# design.net
KiCad netlist of a schematic drawn in EasyEDA
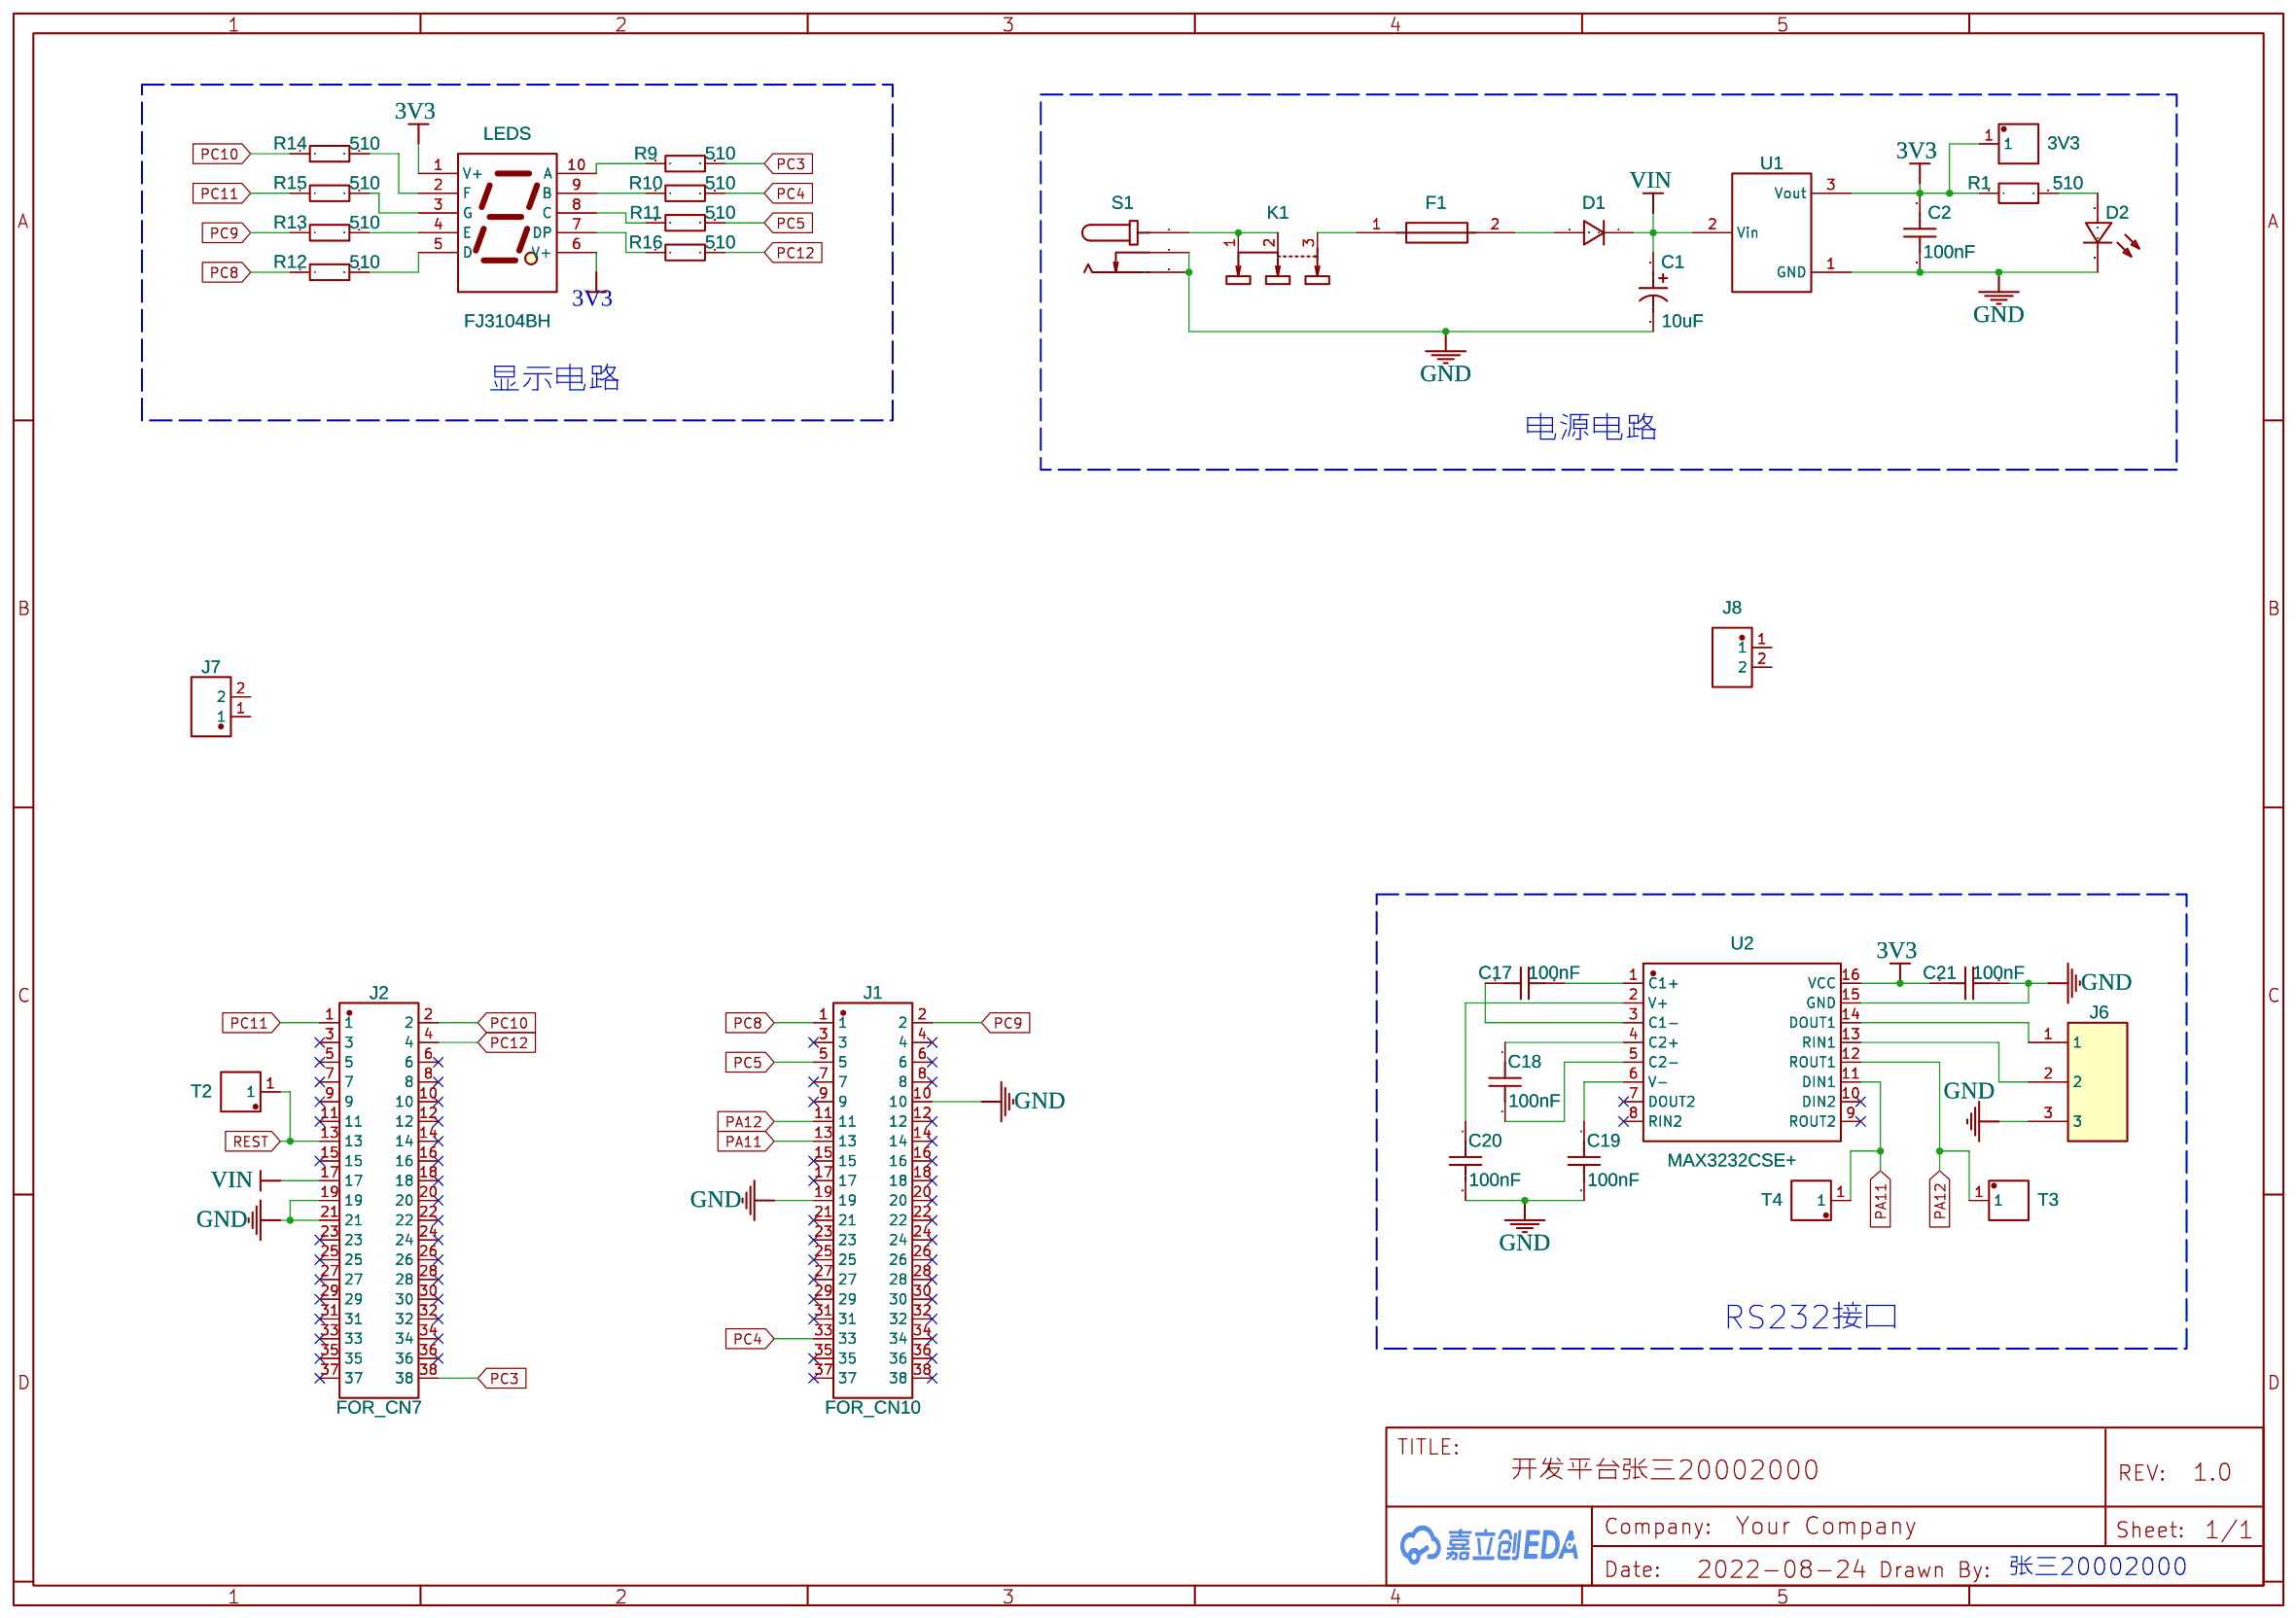
[diagram p0: schematic sheet]

(export (version "E")
  (design (tool "Eeschema 10.0.6"))
  (components
    (comp (ref "3V3")
      (value "54101-T06-00")
      (fields (field (name "BOM_Supplier Part") "C213463"))
      (libsource (lib "") (part "54101-T06-00"))
    )
    (comp (ref "C1")
      (value "10uF")
      (fields
        (field (name "BOM_Manufacturer Part") "50V10uF CD110")
        (field (name "BOM_Supplier Part") "C2960200")
      )
      (libsource (lib "") (part "50V10UF CD110"))
    )
    (comp (ref "C2")
      (value "100nF")
      (fields
        (field (name "BOM_Manufacturer Part") "CT4-0805B104K500F3")
        (field (name "BOM_Supplier Part") "C84772")
      )
      (libsource (lib "") (part "CT4-0805B104K500F3_1"))
    )
    (comp (ref "C17")
      (value "100nF")
      (fields
        (field (name "BOM_Manufacturer Part") "CT4-0805B104K500F3")
        (field (name "BOM_Supplier Part") "C84772")
      )
      (libsource (lib "") (part "CT4-0805B104K500F3"))
    )
    (comp (ref "C18")
      (value "100nF")
      (fields
        (field (name "BOM_Manufacturer Part") "CT4-0805B104K500F3")
        (field (name "BOM_Supplier Part") "C84772")
      )
      (libsource (lib "") (part "CT4-0805B104K500F3_1"))
    )
    (comp (ref "C19")
      (value "100nF")
      (fields
        (field (name "BOM_Manufacturer Part") "CT4-0805B104K500F3")
        (field (name "BOM_Supplier Part") "C84772")
      )
      (libsource (lib "") (part "CT4-0805B104K500F3_1"))
    )
    (comp (ref "C20")
      (value "100nF")
      (fields
        (field (name "BOM_Manufacturer Part") "CT4-0805B104K500F3")
        (field (name "BOM_Supplier Part") "C84772")
      )
      (libsource (lib "") (part "CT4-0805B104K500F3_1"))
    )
    (comp (ref "C21")
      (value "100nF")
      (fields
        (field (name "BOM_Manufacturer Part") "CT4-0805B104K500F3")
        (field (name "BOM_Supplier Part") "C84772")
      )
      (libsource (lib "") (part "CT4-0805B104K500F3"))
    )
    (comp (ref "D1")
      (value "1N5817_C169165")
      (fields (field (name "BOM_Manufacturer Part") "1N5817") (field (name "BOM_Supplier Part") "C169165"))
      (libsource (lib "") (part "1N5817_C169165"))
    )
    (comp (ref "D2")
      (value "TJ-L3FYTGHTFCLFLC2R-A5")
      (fields (field (name "BOM_Supplier Part") "C330746"))
      (libsource (lib "") (part "TJ-L3FYTGHTFCLFLC2R-A5"))
    )
    (comp (ref "F1")
      (value "A72-065")
      (fields (field (name "BOM_Supplier Part") "C135426"))
      (libsource (lib "") (part "A72-065"))
    )
    (comp (ref "J1")
      (value "FOR_CN10")
      (fields
        (field (name "BOM_Manufacturer Part") "PM254-2-19-Z-8.5")
        (field (name "BOM_Supplier Part") "C2897420")
      )
      (libsource (lib "") (part "PM254-2-19-Z-8.5"))
    )
    (comp (ref "J2")
      (value "FOR_CN7")
      (fields
        (field (name "BOM_Manufacturer Part") "PM254-2-19-Z-8.5")
        (field (name "BOM_Supplier Part") "C2897420")
      )
      (libsource (lib "") (part "PM254-2-19-Z-8.5"))
    )
    (comp (ref "J6")
      (value "WJ124-3.81-3P")
      (fields (field (name "BOM_Supplier Part") "C36780"))
      (libsource (lib "") (part "WJ124-3.81-3P"))
    )
    (comp (ref "J7")
      (value "WJ124-3.81-2P")
      (fields (field (name "BOM_Supplier Part") "C69811"))
      (libsource (lib "") (part "WJ124-3.81-2P_1"))
    )
    (comp (ref "J8")
      (value "WJ124-3.81-2P")
      (fields (field (name "BOM_Supplier Part") "C69811"))
      (libsource (lib "") (part "WJ124-3.81-2P"))
    )
    (comp (ref "K1")
      (value "SS-12D10L5")
      (fields (field (name "BOM_Supplier Part") "C319012"))
      (libsource (lib "") (part "SS-12D10L5"))
    )
    (comp (ref "LEDS")
      (value "FJ3104BH")
      (fields (field (name "BOM_Supplier Part") "C2938319"))
      (libsource (lib "") (part "FJ3104BH"))
    )
    (comp (ref "R1")
      (value "510")
      (fields
        (field (name "BOM_Manufacturer Part") "MF1/8W-10KΩ±1%T52")
        (field (name "BOM_Supplier Part") "C713919")
      )
      (libsource (lib "") (part "MF1/8W-10KΩ±1%T52"))
    )
    (comp (ref "R9")
      (value "510")
      (fields (field (name "BOM_Supplier Part") "C119149"))
      (libsource (lib "") (part "MF1/8W-43Ω±1% T52"))
    )
    (comp (ref "R10")
      (value "510")
      (fields (field (name "BOM_Supplier Part") "C119149"))
      (libsource (lib "") (part "MF1/8W-43Ω±1% T52"))
    )
    (comp (ref "R11")
      (value "510")
      (fields (field (name "BOM_Supplier Part") "C119149"))
      (libsource (lib "") (part "MF1/8W-43Ω±1% T52"))
    )
    (comp (ref "R12")
      (value "510")
      (fields (field (name "BOM_Supplier Part") "C119149"))
      (libsource (lib "") (part "MF1/8W-43Ω±1% T52"))
    )
    (comp (ref "R13")
      (value "510")
      (fields (field (name "BOM_Supplier Part") "C119149"))
      (libsource (lib "") (part "MF1/8W-43Ω±1% T52"))
    )
    (comp (ref "R14")
      (value "510")
      (fields (field (name "BOM_Supplier Part") "C119149"))
      (libsource (lib "") (part "MF1/8W-43Ω±1% T52"))
    )
    (comp (ref "R15")
      (value "510")
      (fields (field (name "BOM_Supplier Part") "C119149"))
      (libsource (lib "") (part "MF1/8W-43Ω±1% T52"))
    )
    (comp (ref "R16")
      (value "510")
      (fields (field (name "BOM_Supplier Part") "C119149"))
      (libsource (lib "") (part "MF1/8W-43Ω±1% T52"))
    )
    (comp (ref "S1")
      (value "JPD1030-N521-4F")
      (fields (field (name "BOM_Supplier Part") "C426213"))
      (libsource (lib "") (part "JPD1030-N521-4F"))
    )
    (comp (ref "T2")
      (value "54101-T06-00")
      (fields (field (name "BOM_Supplier Part") "C213463"))
      (libsource (lib "") (part "54101-T06-00_2"))
    )
    (comp (ref "T3")
      (value "54101-T06-00")
      (fields (field (name "BOM_Supplier Part") "C213463"))
      (libsource (lib "") (part "54101-T06-00_1"))
    )
    (comp (ref "T4")
      (value "54101-T06-00")
      (fields (field (name "BOM_Supplier Part") "C213463"))
      (libsource (lib "") (part "54101-T06-00_2"))
    )
    (comp (ref "U1")
      (value "HT7533-1_C32617")
      (fields (field (name "BOM_Manufacturer Part") "HT7533-1") (field (name "BOM_Supplier Part") "C32617"))
      (libsource (lib "") (part "HT7533-1_C32617"))
    )
    (comp (ref "U2")
      (value "MAX3232CSE+")
      (fields (field (name "BOM_Supplier Part") "C143430"))
      (libsource (lib "") (part "MAX3232CSE+"))
    )
  )
  (nets
    (net (code "1") (name "3V3") (class "Default")
      (node (ref "3V3") (pin "1") (pinfunction "1_1") (pintype "unspecified"))
      (node (ref "C2") (pin "1") (pinfunction "1_1") (pintype "unspecified"))
      (node (ref "C21") (pin "1") (pinfunction "1_1") (pintype "unspecified"))
      (node (ref "LEDS") (pin "1") (pinfunction "V+_1") (pintype "unspecified"))
      (node (ref "LEDS") (pin "6") (pinfunction "V+_6") (pintype "unspecified"))
      (node (ref "R1") (pin "1") (pinfunction "1_1") (pintype "unspecified"))
      (node (ref "U1") (pin "3") (pinfunction "Vout_3") (pintype "unspecified"))
      (node (ref "U2") (pin "16") (pinfunction "VCC_16") (pintype "unspecified"))
    )
    (net (code "2") (name "GND") (class "Default")
      (node (ref "C1") (pin "2") (pinfunction "2_2") (pintype "input"))
      (node (ref "C19") (pin "2") (pinfunction "2_2") (pintype "unspecified"))
      (node (ref "C2") (pin "2") (pinfunction "2_2") (pintype "unspecified"))
      (node (ref "C20") (pin "2") (pinfunction "2_2") (pintype "unspecified"))
      (node (ref "C21") (pin "2") (pinfunction "2_2") (pintype "unspecified"))
      (node (ref "D2") (pin "2") (pinfunction "2_2") (pintype "unspecified"))
      (node (ref "J1") (pin "10") (pinfunction "10_10") (pintype "unspecified"))
      (node (ref "J1") (pin "19") (pinfunction "19_19") (pintype "unspecified"))
      (node (ref "J2") (pin "19") (pinfunction "19_19") (pintype "unspecified"))
      (node (ref "J2") (pin "21") (pinfunction "21_21") (pintype "unspecified"))
      (node (ref "J6") (pin "3") (pinfunction "3_3") (pintype "input"))
      (node (ref "S1") (pin "2") (pinfunction "2_2") (pintype "unspecified"))
      (node (ref "S1") (pin "3") (pinfunction "3_3") (pintype "unspecified"))
      (node (ref "U1") (pin "1") (pinfunction "GND_1") (pintype "unspecified"))
      (node (ref "U2") (pin "15") (pinfunction "GND_15") (pintype "unspecified"))
    )
    (net (code "3") (name "Net-(D1-Pad2)") (class "Default")
      (node (ref "D1") (pin "2") (pinfunction "2_2") (pintype "unspecified"))
      (node (ref "F1") (pin "2") (pinfunction "2_2") (pintype "unspecified"))
    )
    (net (code "4") (name "Net-(D2-Pad1)") (class "Default")
      (node (ref "D2") (pin "1") (pinfunction "1_1") (pintype "unspecified"))
      (node (ref "R1") (pin "2") (pinfunction "2_2") (pintype "unspecified"))
    )
    (net (code "5") (name "Net-(F1-Pad1)") (class "Default")
      (node (ref "F1") (pin "1") (pinfunction "1_1") (pintype "unspecified"))
      (node (ref "K1") (pin "3") (pinfunction "3_3") (pintype "unspecified"))
    )
    (net (code "6") (name "Net-(K1-Pad1)") (class "Default")
      (node (ref "K1") (pin "1") (pinfunction "1_1") (pintype "unspecified"))
      (node (ref "K1") (pin "2") (pinfunction "2_2") (pintype "unspecified"))
      (node (ref "S1") (pin "1") (pinfunction "1_1") (pintype "unspecified"))
    )
    (net (code "7") (name "Net-(LEDS-A)") (class "Default")
      (node (ref "LEDS") (pin "10") (pinfunction "A_10") (pintype "unspecified"))
      (node (ref "R9") (pin "1") (pinfunction "1_1") (pintype "unspecified"))
    )
    (net (code "8") (name "Net-(LEDS-B)") (class "Default")
      (node (ref "LEDS") (pin "9") (pinfunction "B_9") (pintype "unspecified"))
      (node (ref "R10") (pin "1") (pinfunction "1_1") (pintype "unspecified"))
    )
    (net (code "9") (name "Net-(LEDS-C)") (class "Default")
      (node (ref "LEDS") (pin "8") (pinfunction "C_8") (pintype "unspecified"))
      (node (ref "R11") (pin "1") (pinfunction "1_1") (pintype "unspecified"))
    )
    (net (code "10") (name "Net-(LEDS-D)") (class "Default")
      (node (ref "LEDS") (pin "5") (pinfunction "D_5") (pintype "unspecified"))
      (node (ref "R12") (pin "2") (pinfunction "2_2") (pintype "unspecified"))
    )
    (net (code "11") (name "Net-(LEDS-DP)") (class "Default")
      (node (ref "LEDS") (pin "7") (pinfunction "DP_7") (pintype "unspecified"))
      (node (ref "R16") (pin "1") (pinfunction "1_1") (pintype "unspecified"))
    )
    (net (code "12") (name "Net-(LEDS-E)") (class "Default")
      (node (ref "LEDS") (pin "4") (pinfunction "E_4") (pintype "unspecified"))
      (node (ref "R13") (pin "2") (pinfunction "2_2") (pintype "unspecified"))
    )
    (net (code "13") (name "Net-(LEDS-F)") (class "Default")
      (node (ref "LEDS") (pin "2") (pinfunction "F_2") (pintype "unspecified"))
      (node (ref "R14") (pin "2") (pinfunction "2_2") (pintype "unspecified"))
    )
    (net (code "14") (name "Net-(LEDS-G)") (class "Default")
      (node (ref "LEDS") (pin "3") (pinfunction "G_3") (pintype "unspecified"))
      (node (ref "R15") (pin "2") (pinfunction "2_2") (pintype "unspecified"))
    )
    (net (code "15") (name "Net-(U2-C1+)") (class "Default")
      (node (ref "C17") (pin "2") (pinfunction "2_2") (pintype "unspecified"))
      (node (ref "U2") (pin "1") (pinfunction "C1+_1") (pintype "unspecified"))
    )
    (net (code "16") (name "Net-(U2-C1-)") (class "Default")
      (node (ref "C17") (pin "1") (pinfunction "1_1") (pintype "unspecified"))
      (node (ref "U2") (pin "3") (pinfunction "C1-_3") (pintype "unspecified"))
    )
    (net (code "17") (name "Net-(U2-C2+)") (class "Default")
      (node (ref "C18") (pin "1") (pinfunction "1_1") (pintype "unspecified"))
      (node (ref "U2") (pin "4") (pinfunction "C2+_4") (pintype "unspecified"))
    )
    (net (code "18") (name "Net-(U2-C2-)") (class "Default")
      (node (ref "C18") (pin "2") (pinfunction "2_2") (pintype "unspecified"))
      (node (ref "U2") (pin "5") (pinfunction "C2-_5") (pintype "unspecified"))
    )
    (net (code "19") (name "Net-(U2-DOUT1)") (class "Default")
      (node (ref "J6") (pin "1") (pinfunction "1_1") (pintype "input"))
      (node (ref "U2") (pin "14") (pinfunction "DOUT1_14") (pintype "unspecified"))
    )
    (net (code "20") (name "Net-(U2-RIN1)") (class "Default")
      (node (ref "J6") (pin "2") (pinfunction "2_2") (pintype "input"))
      (node (ref "U2") (pin "13") (pinfunction "RIN1_13") (pintype "unspecified"))
    )
    (net (code "21") (name "Net-(U2-V+)") (class "Default")
      (node (ref "C20") (pin "1") (pinfunction "1_1") (pintype "unspecified"))
      (node (ref "U2") (pin "2") (pinfunction "V+_2") (pintype "unspecified"))
    )
    (net (code "22") (name "Net-(U2-V-)") (class "Default")
      (node (ref "C19") (pin "1") (pinfunction "1_1") (pintype "unspecified"))
      (node (ref "U2") (pin "6") (pinfunction "V-_6") (pintype "unspecified"))
    )
    (net (code "23") (name "PA11") (class "Default")
      (node (ref "J1") (pin "13") (pinfunction "13_13") (pintype "unspecified"))
      (node (ref "T4") (pin "1") (pinfunction "1_1") (pintype "unspecified"))
      (node (ref "U2") (pin "11") (pinfunction "DIN1_11") (pintype "unspecified"))
    )
    (net (code "24") (name "PA12") (class "Default")
      (node (ref "J1") (pin "11") (pinfunction "11_11") (pintype "unspecified"))
      (node (ref "T3") (pin "1") (pinfunction "1_1") (pintype "unspecified"))
      (node (ref "U2") (pin "12") (pinfunction "ROUT1_12") (pintype "unspecified"))
    )
    (net (code "25") (name "PC3") (class "Default")
      (node (ref "J2") (pin "38") (pinfunction "38_38") (pintype "unspecified"))
      (node (ref "R9") (pin "2") (pinfunction "2_2") (pintype "unspecified"))
    )
    (net (code "26") (name "PC4") (class "Default")
      (node (ref "J1") (pin "33") (pinfunction "33_33") (pintype "unspecified"))
      (node (ref "R10") (pin "2") (pinfunction "2_2") (pintype "unspecified"))
    )
    (net (code "27") (name "PC5") (class "Default")
      (node (ref "J1") (pin "5") (pinfunction "5_5") (pintype "unspecified"))
      (node (ref "R11") (pin "2") (pinfunction "2_2") (pintype "unspecified"))
    )
    (net (code "28") (name "PC8") (class "Default")
      (node (ref "J1") (pin "1") (pinfunction "1_1") (pintype "unspecified"))
      (node (ref "R12") (pin "1") (pinfunction "1_1") (pintype "unspecified"))
    )
    (net (code "29") (name "PC9") (class "Default")
      (node (ref "J1") (pin "2") (pinfunction "2_2") (pintype "unspecified"))
      (node (ref "R13") (pin "1") (pinfunction "1_1") (pintype "unspecified"))
    )
    (net (code "30") (name "PC10") (class "Default")
      (node (ref "J2") (pin "2") (pinfunction "2_2") (pintype "unspecified"))
      (node (ref "R14") (pin "1") (pinfunction "1_1") (pintype "unspecified"))
    )
    (net (code "31") (name "PC11") (class "Default")
      (node (ref "J2") (pin "1") (pinfunction "1_1") (pintype "unspecified"))
      (node (ref "R15") (pin "1") (pinfunction "1_1") (pintype "unspecified"))
    )
    (net (code "32") (name "PC12") (class "Default")
      (node (ref "J2") (pin "4") (pinfunction "4_4") (pintype "unspecified"))
      (node (ref "R16") (pin "2") (pinfunction "2_2") (pintype "unspecified"))
    )
    (net (code "33") (name "REST") (class "Default")
      (node (ref "J2") (pin "13") (pinfunction "13_13") (pintype "unspecified"))
      (node (ref "T2") (pin "1") (pinfunction "1_1") (pintype "unspecified"))
    )
    (net (code "34") (name "VIN") (class "Default")
      (node (ref "C1") (pin "1") (pinfunction "1_1") (pintype "input"))
      (node (ref "D1") (pin "1") (pinfunction "1_1") (pintype "unspecified"))
      (node (ref "J2") (pin "17") (pinfunction "17_17") (pintype "unspecified"))
      (node (ref "U1") (pin "2") (pinfunction "Vin_2") (pintype "unspecified"))
    )
    (net (code "35") (name "unconnected-(J1-Pad3)") (class "Default")
      (node (ref "J1") (pin "3") (pinfunction "3_3") (pintype "unspecified+no_connect"))
    )
    (net (code "36") (name "unconnected-(J1-Pad4)") (class "Default")
      (node (ref "J1") (pin "4") (pinfunction "4_4") (pintype "unspecified+no_connect"))
    )
    (net (code "37") (name "unconnected-(J1-Pad6)") (class "Default")
      (node (ref "J1") (pin "6") (pinfunction "6_6") (pintype "unspecified+no_connect"))
    )
    (net (code "38") (name "unconnected-(J1-Pad7)") (class "Default")
      (node (ref "J1") (pin "7") (pinfunction "7_7") (pintype "unspecified+no_connect"))
    )
    (net (code "39") (name "unconnected-(J1-Pad8)") (class "Default")
      (node (ref "J1") (pin "8") (pinfunction "8_8") (pintype "unspecified+no_connect"))
    )
    (net (code "40") (name "unconnected-(J1-Pad9)") (class "Default")
      (node (ref "J1") (pin "9") (pinfunction "9_9") (pintype "unspecified+no_connect"))
    )
    (net (code "41") (name "unconnected-(J1-Pad12)") (class "Default")
      (node (ref "J1") (pin "12") (pinfunction "12_12") (pintype "unspecified+no_connect"))
    )
    (net (code "42") (name "unconnected-(J1-Pad14)") (class "Default")
      (node (ref "J1") (pin "14") (pinfunction "14_14") (pintype "unspecified+no_connect"))
    )
    (net (code "43") (name "unconnected-(J1-Pad15)") (class "Default")
      (node (ref "J1") (pin "15") (pinfunction "15_15") (pintype "unspecified+no_connect"))
    )
    (net (code "44") (name "unconnected-(J1-Pad16)") (class "Default")
      (node (ref "J1") (pin "16") (pinfunction "16_16") (pintype "unspecified+no_connect"))
    )
    (net (code "45") (name "unconnected-(J1-Pad17)") (class "Default")
      (node (ref "J1") (pin "17") (pinfunction "17_17") (pintype "unspecified+no_connect"))
    )
    (net (code "46") (name "unconnected-(J1-Pad18)") (class "Default")
      (node (ref "J1") (pin "18") (pinfunction "18_18") (pintype "unspecified+no_connect"))
    )
    (net (code "47") (name "unconnected-(J1-Pad20)") (class "Default")
      (node (ref "J1") (pin "20") (pinfunction "20_20") (pintype "unspecified+no_connect"))
    )
    (net (code "48") (name "unconnected-(J1-Pad21)") (class "Default")
      (node (ref "J1") (pin "21") (pinfunction "21_21") (pintype "unspecified+no_connect"))
    )
    (net (code "49") (name "unconnected-(J1-Pad22)") (class "Default")
      (node (ref "J1") (pin "22") (pinfunction "22_22") (pintype "unspecified+no_connect"))
    )
    (net (code "50") (name "unconnected-(J1-Pad23)") (class "Default")
      (node (ref "J1") (pin "23") (pinfunction "23_23") (pintype "unspecified+no_connect"))
    )
    (net (code "51") (name "unconnected-(J1-Pad24)") (class "Default")
      (node (ref "J1") (pin "24") (pinfunction "24_24") (pintype "unspecified+no_connect"))
    )
    (net (code "52") (name "unconnected-(J1-Pad25)") (class "Default")
      (node (ref "J1") (pin "25") (pinfunction "25_25") (pintype "unspecified+no_connect"))
    )
    (net (code "53") (name "unconnected-(J1-Pad26)") (class "Default")
      (node (ref "J1") (pin "26") (pinfunction "26_26") (pintype "unspecified+no_connect"))
    )
    (net (code "54") (name "unconnected-(J1-Pad27)") (class "Default")
      (node (ref "J1") (pin "27") (pinfunction "27_27") (pintype "unspecified+no_connect"))
    )
    (net (code "55") (name "unconnected-(J1-Pad28)") (class "Default")
      (node (ref "J1") (pin "28") (pinfunction "28_28") (pintype "unspecified+no_connect"))
    )
    (net (code "56") (name "unconnected-(J1-Pad29)") (class "Default")
      (node (ref "J1") (pin "29") (pinfunction "29_29") (pintype "unspecified+no_connect"))
    )
    (net (code "57") (name "unconnected-(J1-Pad30)") (class "Default")
      (node (ref "J1") (pin "30") (pinfunction "30_30") (pintype "unspecified+no_connect"))
    )
    (net (code "58") (name "unconnected-(J1-Pad31)") (class "Default")
      (node (ref "J1") (pin "31") (pinfunction "31_31") (pintype "unspecified+no_connect"))
    )
    (net (code "59") (name "unconnected-(J1-Pad32)") (class "Default")
      (node (ref "J1") (pin "32") (pinfunction "32_32") (pintype "unspecified+no_connect"))
    )
    (net (code "60") (name "unconnected-(J1-Pad34)") (class "Default")
      (node (ref "J1") (pin "34") (pinfunction "34_34") (pintype "unspecified+no_connect"))
    )
    (net (code "61") (name "unconnected-(J1-Pad35)") (class "Default")
      (node (ref "J1") (pin "35") (pinfunction "35_35") (pintype "unspecified+no_connect"))
    )
    (net (code "62") (name "unconnected-(J1-Pad36)") (class "Default")
      (node (ref "J1") (pin "36") (pinfunction "36_36") (pintype "unspecified+no_connect"))
    )
    (net (code "63") (name "unconnected-(J1-Pad37)") (class "Default")
      (node (ref "J1") (pin "37") (pinfunction "37_37") (pintype "unspecified+no_connect"))
    )
    (net (code "64") (name "unconnected-(J1-Pad38)") (class "Default")
      (node (ref "J1") (pin "38") (pinfunction "38_38") (pintype "unspecified+no_connect"))
    )
    (net (code "65") (name "unconnected-(J2-Pad3)") (class "Default")
      (node (ref "J2") (pin "3") (pinfunction "3_3") (pintype "unspecified+no_connect"))
    )
    (net (code "66") (name "unconnected-(J2-Pad5)") (class "Default")
      (node (ref "J2") (pin "5") (pinfunction "5_5") (pintype "unspecified+no_connect"))
    )
    (net (code "67") (name "unconnected-(J2-Pad6)") (class "Default")
      (node (ref "J2") (pin "6") (pinfunction "6_6") (pintype "unspecified+no_connect"))
    )
    (net (code "68") (name "unconnected-(J2-Pad7)") (class "Default")
      (node (ref "J2") (pin "7") (pinfunction "7_7") (pintype "unspecified+no_connect"))
    )
    (net (code "69") (name "unconnected-(J2-Pad8)") (class "Default")
      (node (ref "J2") (pin "8") (pinfunction "8_8") (pintype "unspecified+no_connect"))
    )
    (net (code "70") (name "unconnected-(J2-Pad9)") (class "Default")
      (node (ref "J2") (pin "9") (pinfunction "9_9") (pintype "unspecified+no_connect"))
    )
    (net (code "71") (name "unconnected-(J2-Pad10)") (class "Default")
      (node (ref "J2") (pin "10") (pinfunction "10_10") (pintype "unspecified+no_connect"))
    )
    (net (code "72") (name "unconnected-(J2-Pad11)") (class "Default")
      (node (ref "J2") (pin "11") (pinfunction "11_11") (pintype "unspecified+no_connect"))
    )
    (net (code "73") (name "unconnected-(J2-Pad12)") (class "Default")
      (node (ref "J2") (pin "12") (pinfunction "12_12") (pintype "unspecified+no_connect"))
    )
    (net (code "74") (name "unconnected-(J2-Pad14)") (class "Default")
      (node (ref "J2") (pin "14") (pinfunction "14_14") (pintype "unspecified+no_connect"))
    )
    (net (code "75") (name "unconnected-(J2-Pad15)") (class "Default")
      (node (ref "J2") (pin "15") (pinfunction "15_15") (pintype "unspecified+no_connect"))
    )
    (net (code "76") (name "unconnected-(J2-Pad16)") (class "Default")
      (node (ref "J2") (pin "16") (pinfunction "16_16") (pintype "unspecified+no_connect"))
    )
    (net (code "77") (name "unconnected-(J2-Pad18)") (class "Default")
      (node (ref "J2") (pin "18") (pinfunction "18_18") (pintype "unspecified+no_connect"))
    )
    (net (code "78") (name "unconnected-(J2-Pad20)") (class "Default")
      (node (ref "J2") (pin "20") (pinfunction "20_20") (pintype "unspecified+no_connect"))
    )
    (net (code "79") (name "unconnected-(J2-Pad22)") (class "Default")
      (node (ref "J2") (pin "22") (pinfunction "22_22") (pintype "unspecified+no_connect"))
    )
    (net (code "80") (name "unconnected-(J2-Pad23)") (class "Default")
      (node (ref "J2") (pin "23") (pinfunction "23_23") (pintype "unspecified+no_connect"))
    )
    (net (code "81") (name "unconnected-(J2-Pad24)") (class "Default")
      (node (ref "J2") (pin "24") (pinfunction "24_24") (pintype "unspecified+no_connect"))
    )
    (net (code "82") (name "unconnected-(J2-Pad25)") (class "Default")
      (node (ref "J2") (pin "25") (pinfunction "25_25") (pintype "unspecified+no_connect"))
    )
    (net (code "83") (name "unconnected-(J2-Pad26)") (class "Default")
      (node (ref "J2") (pin "26") (pinfunction "26_26") (pintype "unspecified+no_connect"))
    )
    (net (code "84") (name "unconnected-(J2-Pad27)") (class "Default")
      (node (ref "J2") (pin "27") (pinfunction "27_27") (pintype "unspecified+no_connect"))
    )
    (net (code "85") (name "unconnected-(J2-Pad28)") (class "Default")
      (node (ref "J2") (pin "28") (pinfunction "28_28") (pintype "unspecified+no_connect"))
    )
    (net (code "86") (name "unconnected-(J2-Pad29)") (class "Default")
      (node (ref "J2") (pin "29") (pinfunction "29_29") (pintype "unspecified+no_connect"))
    )
    (net (code "87") (name "unconnected-(J2-Pad30)") (class "Default")
      (node (ref "J2") (pin "30") (pinfunction "30_30") (pintype "unspecified+no_connect"))
    )
    (net (code "88") (name "unconnected-(J2-Pad31)") (class "Default")
      (node (ref "J2") (pin "31") (pinfunction "31_31") (pintype "unspecified+no_connect"))
    )
    (net (code "89") (name "unconnected-(J2-Pad32)") (class "Default")
      (node (ref "J2") (pin "32") (pinfunction "32_32") (pintype "unspecified+no_connect"))
    )
    (net (code "90") (name "unconnected-(J2-Pad33)") (class "Default")
      (node (ref "J2") (pin "33") (pinfunction "33_33") (pintype "unspecified+no_connect"))
    )
    (net (code "91") (name "unconnected-(J2-Pad34)") (class "Default")
      (node (ref "J2") (pin "34") (pinfunction "34_34") (pintype "unspecified+no_connect"))
    )
    (net (code "92") (name "unconnected-(J2-Pad35)") (class "Default")
      (node (ref "J2") (pin "35") (pinfunction "35_35") (pintype "unspecified+no_connect"))
    )
    (net (code "93") (name "unconnected-(J2-Pad36)") (class "Default")
      (node (ref "J2") (pin "36") (pinfunction "36_36") (pintype "unspecified+no_connect"))
    )
    (net (code "94") (name "unconnected-(J2-Pad37)") (class "Default")
      (node (ref "J2") (pin "37") (pinfunction "37_37") (pintype "unspecified+no_connect"))
    )
    (net (code "95") (name "unconnected-(J7-Pad1)") (class "Default")
      (node (ref "J7") (pin "1") (pinfunction "1_1") (pintype "unspecified"))
    )
    (net (code "96") (name "unconnected-(J7-Pad2)") (class "Default")
      (node (ref "J7") (pin "2") (pinfunction "2_2") (pintype "unspecified"))
    )
    (net (code "97") (name "unconnected-(J8-Pad1)") (class "Default")
      (node (ref "J8") (pin "1") (pinfunction "1_1") (pintype "unspecified"))
    )
    (net (code "98") (name "unconnected-(J8-Pad2)") (class "Default")
      (node (ref "J8") (pin "2") (pinfunction "2_2") (pintype "unspecified"))
    )
    (net (code "99") (name "unconnected-(U2-DIN2-Pad10)") (class "Default")
      (node (ref "U2") (pin "10") (pinfunction "DIN2_10") (pintype "unspecified+no_connect"))
    )
    (net (code "100") (name "unconnected-(U2-DOUT2-Pad7)") (class "Default")
      (node (ref "U2") (pin "7") (pinfunction "DOUT2_7") (pintype "unspecified+no_connect"))
    )
    (net (code "101") (name "unconnected-(U2-RIN2-Pad8)") (class "Default")
      (node (ref "U2") (pin "8") (pinfunction "RIN2_8") (pintype "unspecified+no_connect"))
    )
    (net (code "102") (name "unconnected-(U2-ROUT2-Pad9)") (class "Default")
      (node (ref "U2") (pin "9") (pinfunction "ROUT2_9") (pintype "unspecified+no_connect"))
    )
  )
)
